# Sheet1.net
KiCad netlist of a schematic drawn in Altium Designer
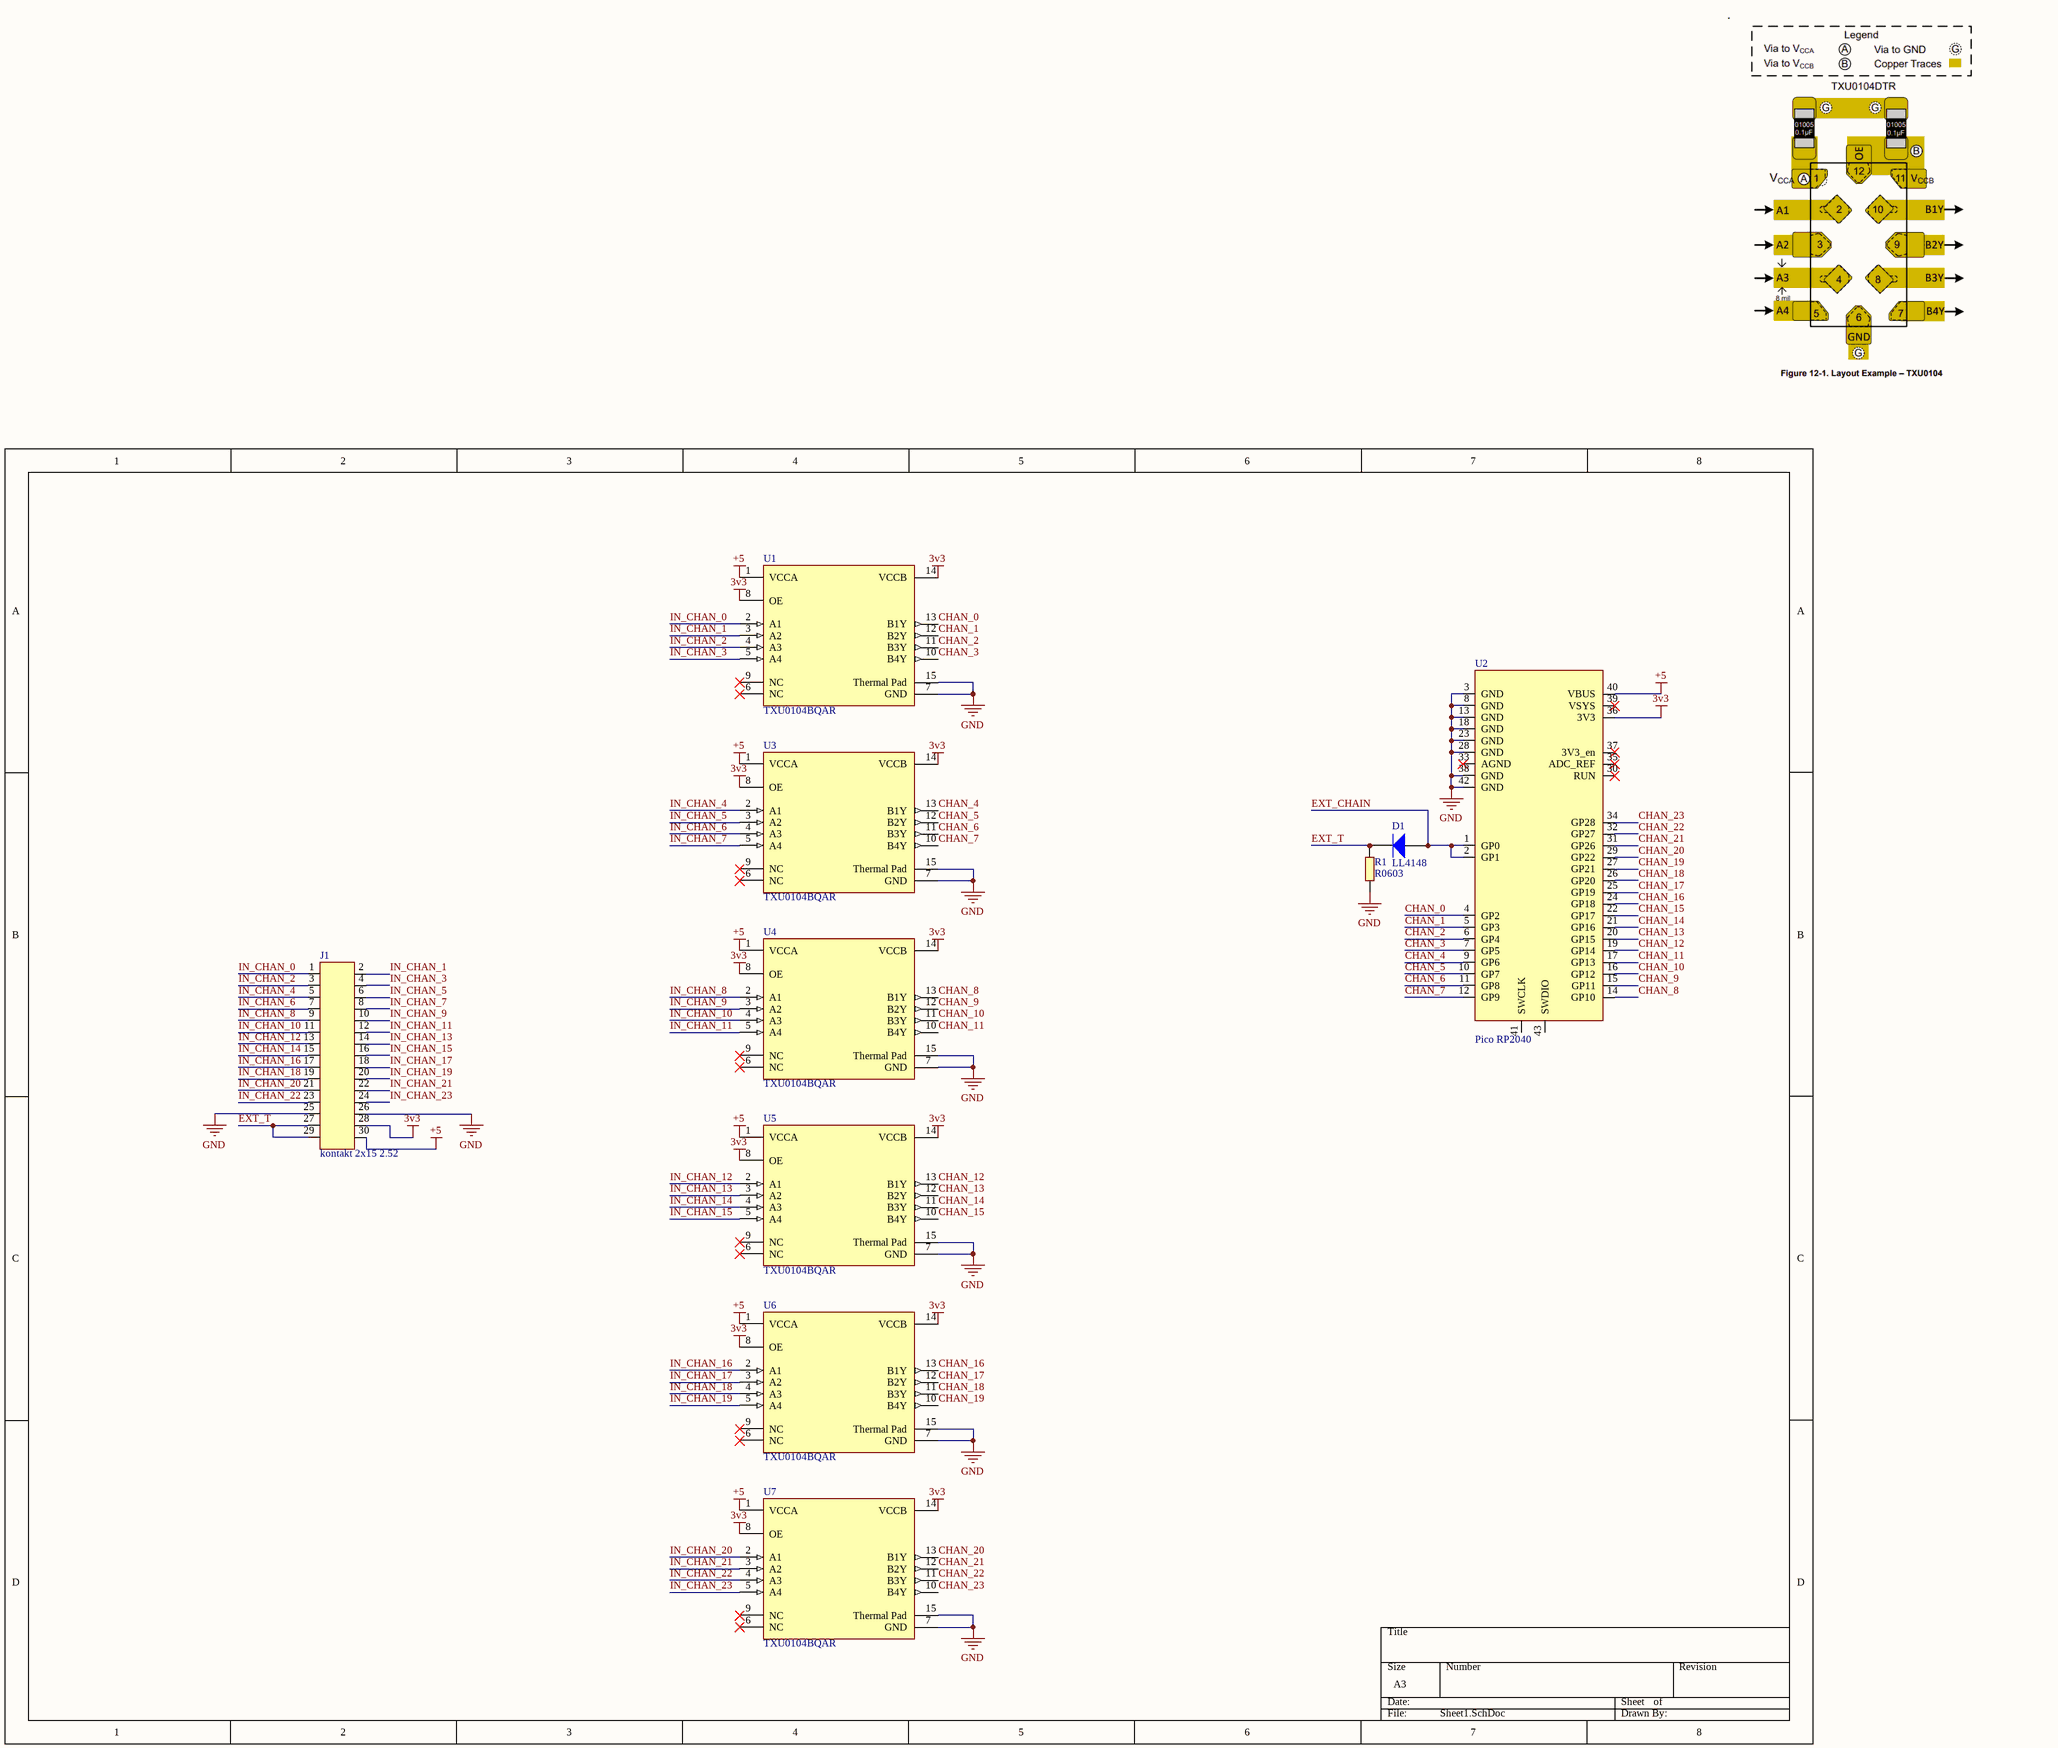
[diagram p0: Sheet1.SchDoc]

(export (version "E")
  (design (tool "Eeschema 10.0.6"))
  (components
    (comp (ref "D1")
      (value "LL4148")
      (footprint "FAIR-SOD80-2_V")
      (description "Small Signal Diode, 100 V, 0.2 A, -55 to 175 degC, 2-Pin SOD80, RoHS, Tape and Reel")
      (fields (field (name "MANUFACTURER") "Fairchild"))
      (libsource (lib "Altium Content Vault") (part "D-AK-2"))
    )
    (comp (ref "J1") (value "kontakt 2x15 2.52") (libsource (lib "Schlib1") (part "kontakt 2x15 2.52")))
    (comp (ref "R1") (value "R0603") (footprint "Res 0603") (libsource (lib "Schlib1") (part "R0603")))
    (comp (ref "U1")
      (value "TXU0104BQAR")
      (footprint "FP-BQA0014A-MFG")
      (description "FOUR CHANNEL UNIDIRECTIONAL LEVE")
      (libsource (lib "Altium Content Vault") (part "484c88173ff96930f3332f938e5da47"))
    )
    (comp (ref "U2")
      (value "Pico RP2040")
      (footprint "raspberry pico solder plate")
      (libsource (lib "Schlib1") (part "Pico RP2040"))
    )
    (comp (ref "U3")
      (value "TXU0104BQAR")
      (footprint "FP-BQA0014A-MFG")
      (description "FOUR CHANNEL UNIDIRECTIONAL LEVE")
      (libsource (lib "Altium Content Vault") (part "484c88173ff96930f3332f938e5da47"))
    )
    (comp (ref "U4")
      (value "TXU0104BQAR")
      (footprint "FP-BQA0014A-MFG")
      (description "FOUR CHANNEL UNIDIRECTIONAL LEVE")
      (libsource (lib "Altium Content Vault") (part "484c88173ff96930f3332f938e5da47"))
    )
    (comp (ref "U5")
      (value "TXU0104BQAR")
      (footprint "FP-BQA0014A-MFG")
      (description "FOUR CHANNEL UNIDIRECTIONAL LEVE")
      (libsource (lib "Altium Content Vault") (part "484c88173ff96930f3332f938e5da47"))
    )
    (comp (ref "U6")
      (value "TXU0104BQAR")
      (footprint "FP-BQA0014A-MFG")
      (description "FOUR CHANNEL UNIDIRECTIONAL LEVE")
      (libsource (lib "Altium Content Vault") (part "484c88173ff96930f3332f938e5da47"))
    )
    (comp (ref "U7")
      (value "TXU0104BQAR")
      (footprint "FP-BQA0014A-MFG")
      (description "FOUR CHANNEL UNIDIRECTIONAL LEVE")
      (libsource (lib "Altium Content Vault") (part "484c88173ff96930f3332f938e5da47"))
    )
  )
  (nets
    (net (code "1") (name "+5") (class "Default")
      (node (ref "J1") (pin "30") (pinfunction "30_30") (pintype "passive"))
      (node (ref "U1") (pin "1") (pinfunction "VCCA_1") (pintype "power_in"))
      (node (ref "U2") (pin "40") (pinfunction "VBUS_40") (pintype "passive"))
      (node (ref "U3") (pin "1") (pinfunction "VCCA_1") (pintype "power_in"))
      (node (ref "U4") (pin "1") (pinfunction "VCCA_1") (pintype "power_in"))
      (node (ref "U5") (pin "1") (pinfunction "VCCA_1") (pintype "power_in"))
      (node (ref "U6") (pin "1") (pinfunction "VCCA_1") (pintype "power_in"))
      (node (ref "U7") (pin "1") (pinfunction "VCCA_1") (pintype "power_in"))
    )
    (net (code "2") (name "/CHAN_0") (class "Default")
      (node (ref "U1") (pin "13") (pinfunction "B1Y_13") (pintype "output"))
      (node (ref "U2") (pin "4") (pinfunction "GP2_4") (pintype "passive"))
    )
    (net (code "3") (name "/CHAN_1") (class "Default")
      (node (ref "U1") (pin "12") (pinfunction "B2Y_12") (pintype "output"))
      (node (ref "U2") (pin "5") (pinfunction "GP3_5") (pintype "passive"))
    )
    (net (code "4") (name "/CHAN_2") (class "Default")
      (node (ref "U1") (pin "11") (pinfunction "B3Y_11") (pintype "output"))
      (node (ref "U2") (pin "6") (pinfunction "GP4_6") (pintype "passive"))
    )
    (net (code "5") (name "/CHAN_3") (class "Default")
      (node (ref "U1") (pin "10") (pinfunction "B4Y_10") (pintype "output"))
      (node (ref "U2") (pin "7") (pinfunction "GP5_7") (pintype "passive"))
    )
    (net (code "6") (name "/CHAN_4") (class "Default")
      (node (ref "U2") (pin "9") (pinfunction "GP6_9") (pintype "passive"))
      (node (ref "U3") (pin "13") (pinfunction "B1Y_13") (pintype "output"))
    )
    (net (code "7") (name "/CHAN_5") (class "Default")
      (node (ref "U2") (pin "10") (pinfunction "GP7_10") (pintype "passive"))
      (node (ref "U3") (pin "12") (pinfunction "B2Y_12") (pintype "output"))
    )
    (net (code "8") (name "/CHAN_6") (class "Default")
      (node (ref "U2") (pin "11") (pinfunction "GP8_11") (pintype "passive"))
      (node (ref "U3") (pin "11") (pinfunction "B3Y_11") (pintype "output"))
    )
    (net (code "9") (name "/CHAN_7") (class "Default")
      (node (ref "U2") (pin "12") (pinfunction "GP9_12") (pintype "passive"))
      (node (ref "U3") (pin "10") (pinfunction "B4Y_10") (pintype "output"))
    )
    (net (code "10") (name "/CHAN_8") (class "Default")
      (node (ref "U2") (pin "14") (pinfunction "GP10_14") (pintype "passive"))
      (node (ref "U4") (pin "13") (pinfunction "B1Y_13") (pintype "output"))
    )
    (net (code "11") (name "/CHAN_9") (class "Default")
      (node (ref "U2") (pin "15") (pinfunction "GP11_15") (pintype "passive"))
      (node (ref "U4") (pin "12") (pinfunction "B2Y_12") (pintype "output"))
    )
    (net (code "12") (name "/CHAN_10") (class "Default")
      (node (ref "U2") (pin "16") (pinfunction "GP12_16") (pintype "passive"))
      (node (ref "U4") (pin "11") (pinfunction "B3Y_11") (pintype "output"))
    )
    (net (code "13") (name "/CHAN_11") (class "Default")
      (node (ref "U2") (pin "17") (pinfunction "GP13_17") (pintype "passive"))
      (node (ref "U4") (pin "10") (pinfunction "B4Y_10") (pintype "output"))
    )
    (net (code "14") (name "/CHAN_12") (class "Default")
      (node (ref "U2") (pin "19") (pinfunction "GP14_19") (pintype "passive"))
      (node (ref "U5") (pin "13") (pinfunction "B1Y_13") (pintype "output"))
    )
    (net (code "15") (name "/CHAN_13") (class "Default")
      (node (ref "U2") (pin "20") (pinfunction "GP15_20") (pintype "passive"))
      (node (ref "U5") (pin "12") (pinfunction "B2Y_12") (pintype "output"))
    )
    (net (code "16") (name "/CHAN_14") (class "Default")
      (node (ref "U2") (pin "21") (pinfunction "GP16_21") (pintype "passive"))
      (node (ref "U5") (pin "11") (pinfunction "B3Y_11") (pintype "output"))
    )
    (net (code "17") (name "/CHAN_15") (class "Default")
      (node (ref "U2") (pin "22") (pinfunction "GP17_22") (pintype "passive"))
      (node (ref "U5") (pin "10") (pinfunction "B4Y_10") (pintype "output"))
    )
    (net (code "18") (name "/CHAN_16") (class "Default")
      (node (ref "U2") (pin "24") (pinfunction "GP18_24") (pintype "passive"))
      (node (ref "U6") (pin "13") (pinfunction "B1Y_13") (pintype "output"))
    )
    (net (code "19") (name "/CHAN_17") (class "Default")
      (node (ref "U2") (pin "25") (pinfunction "GP19_25") (pintype "passive"))
      (node (ref "U6") (pin "12") (pinfunction "B2Y_12") (pintype "output"))
    )
    (net (code "20") (name "/CHAN_18") (class "Default")
      (node (ref "U2") (pin "26") (pinfunction "GP20_26") (pintype "passive"))
      (node (ref "U6") (pin "11") (pinfunction "B3Y_11") (pintype "output"))
    )
    (net (code "21") (name "/CHAN_19") (class "Default")
      (node (ref "U2") (pin "27") (pinfunction "GP21_27") (pintype "passive"))
      (node (ref "U6") (pin "10") (pinfunction "B4Y_10") (pintype "output"))
    )
    (net (code "22") (name "/CHAN_20") (class "Default")
      (node (ref "U2") (pin "29") (pinfunction "GP22_29") (pintype "passive"))
      (node (ref "U7") (pin "13") (pinfunction "B1Y_13") (pintype "output"))
    )
    (net (code "23") (name "/CHAN_21") (class "Default")
      (node (ref "U2") (pin "31") (pinfunction "GP26_31") (pintype "passive"))
      (node (ref "U7") (pin "12") (pinfunction "B2Y_12") (pintype "output"))
    )
    (net (code "24") (name "/CHAN_22") (class "Default")
      (node (ref "U2") (pin "32") (pinfunction "GP27_32") (pintype "passive"))
      (node (ref "U7") (pin "11") (pinfunction "B3Y_11") (pintype "output"))
    )
    (net (code "25") (name "/CHAN_23") (class "Default")
      (node (ref "U2") (pin "34") (pinfunction "GP28_34") (pintype "passive"))
      (node (ref "U7") (pin "10") (pinfunction "B4Y_10") (pintype "output"))
    )
    (net (code "26") (name "/EXT_CHAIN") (class "Default")
      (node (ref "D1") (pin "1") (pinfunction "A_1") (pintype "passive"))
      (node (ref "U2") (pin "1") (pinfunction "GP0_1") (pintype "passive"))
      (node (ref "U2") (pin "2") (pinfunction "GP1_2") (pintype "passive"))
    )
    (net (code "27") (name "/EXT_T") (class "Default")
      (node (ref "D1") (pin "2") (pinfunction "K_2") (pintype "passive"))
      (node (ref "J1") (pin "27") (pinfunction "27_27") (pintype "passive"))
      (node (ref "J1") (pin "29") (pinfunction "29_29") (pintype "passive"))
      (node (ref "R1") (pin "2") (pinfunction "2_2") (pintype "passive"))
    )
    (net (code "28") (name "/IN_CHAN_0") (class "Default")
      (node (ref "J1") (pin "1") (pinfunction "1_1") (pintype "passive"))
      (node (ref "U1") (pin "2") (pinfunction "A1_2") (pintype "input"))
    )
    (net (code "29") (name "/IN_CHAN_1") (class "Default")
      (node (ref "J1") (pin "2") (pinfunction "2_2") (pintype "passive"))
      (node (ref "U1") (pin "3") (pinfunction "A2_3") (pintype "input"))
    )
    (net (code "30") (name "/IN_CHAN_2") (class "Default")
      (node (ref "J1") (pin "3") (pinfunction "3_3") (pintype "passive"))
      (node (ref "U1") (pin "4") (pinfunction "A3_4") (pintype "input"))
    )
    (net (code "31") (name "/IN_CHAN_3") (class "Default")
      (node (ref "J1") (pin "4") (pinfunction "4_4") (pintype "passive"))
      (node (ref "U1") (pin "5") (pinfunction "A4_5") (pintype "input"))
    )
    (net (code "32") (name "/IN_CHAN_4") (class "Default")
      (node (ref "J1") (pin "5") (pinfunction "5_5") (pintype "passive"))
      (node (ref "U3") (pin "2") (pinfunction "A1_2") (pintype "input"))
    )
    (net (code "33") (name "/IN_CHAN_5") (class "Default")
      (node (ref "J1") (pin "6") (pinfunction "6_6") (pintype "passive"))
      (node (ref "U3") (pin "3") (pinfunction "A2_3") (pintype "input"))
    )
    (net (code "34") (name "/IN_CHAN_6") (class "Default")
      (node (ref "J1") (pin "7") (pinfunction "7_7") (pintype "passive"))
      (node (ref "U3") (pin "4") (pinfunction "A3_4") (pintype "input"))
    )
    (net (code "35") (name "/IN_CHAN_7") (class "Default")
      (node (ref "J1") (pin "8") (pinfunction "8_8") (pintype "passive"))
      (node (ref "U3") (pin "5") (pinfunction "A4_5") (pintype "input"))
    )
    (net (code "36") (name "/IN_CHAN_8") (class "Default")
      (node (ref "J1") (pin "9") (pinfunction "9_9") (pintype "passive"))
      (node (ref "U4") (pin "2") (pinfunction "A1_2") (pintype "input"))
    )
    (net (code "37") (name "/IN_CHAN_9") (class "Default")
      (node (ref "J1") (pin "10") (pinfunction "10_10") (pintype "passive"))
      (node (ref "U4") (pin "3") (pinfunction "A2_3") (pintype "input"))
    )
    (net (code "38") (name "/IN_CHAN_10") (class "Default")
      (node (ref "J1") (pin "11") (pinfunction "11_11") (pintype "passive"))
      (node (ref "U4") (pin "4") (pinfunction "A3_4") (pintype "input"))
    )
    (net (code "39") (name "/IN_CHAN_11") (class "Default")
      (node (ref "J1") (pin "12") (pinfunction "12_12") (pintype "passive"))
      (node (ref "U4") (pin "5") (pinfunction "A4_5") (pintype "input"))
    )
    (net (code "40") (name "/IN_CHAN_12") (class "Default")
      (node (ref "J1") (pin "13") (pinfunction "13_13") (pintype "passive"))
      (node (ref "U5") (pin "2") (pinfunction "A1_2") (pintype "input"))
    )
    (net (code "41") (name "/IN_CHAN_13") (class "Default")
      (node (ref "J1") (pin "14") (pinfunction "14_14") (pintype "passive"))
      (node (ref "U5") (pin "3") (pinfunction "A2_3") (pintype "input"))
    )
    (net (code "42") (name "/IN_CHAN_14") (class "Default")
      (node (ref "J1") (pin "15") (pinfunction "15_15") (pintype "passive"))
      (node (ref "U5") (pin "4") (pinfunction "A3_4") (pintype "input"))
    )
    (net (code "43") (name "/IN_CHAN_15") (class "Default")
      (node (ref "J1") (pin "16") (pinfunction "16_16") (pintype "passive"))
      (node (ref "U5") (pin "5") (pinfunction "A4_5") (pintype "input"))
    )
    (net (code "44") (name "/IN_CHAN_16") (class "Default")
      (node (ref "J1") (pin "17") (pinfunction "17_17") (pintype "passive"))
      (node (ref "U6") (pin "2") (pinfunction "A1_2") (pintype "input"))
    )
    (net (code "45") (name "/IN_CHAN_17") (class "Default")
      (node (ref "J1") (pin "18") (pinfunction "18_18") (pintype "passive"))
      (node (ref "U6") (pin "3") (pinfunction "A2_3") (pintype "input"))
    )
    (net (code "46") (name "/IN_CHAN_18") (class "Default")
      (node (ref "J1") (pin "19") (pinfunction "19_19") (pintype "passive"))
      (node (ref "U6") (pin "4") (pinfunction "A3_4") (pintype "input"))
    )
    (net (code "47") (name "/IN_CHAN_19") (class "Default")
      (node (ref "J1") (pin "20") (pinfunction "20_20") (pintype "passive"))
      (node (ref "U6") (pin "5") (pinfunction "A4_5") (pintype "input"))
    )
    (net (code "48") (name "/IN_CHAN_20") (class "Default")
      (node (ref "J1") (pin "21") (pinfunction "21_21") (pintype "passive"))
      (node (ref "U7") (pin "2") (pinfunction "A1_2") (pintype "input"))
    )
    (net (code "49") (name "/IN_CHAN_21") (class "Default")
      (node (ref "J1") (pin "22") (pinfunction "22_22") (pintype "passive"))
      (node (ref "U7") (pin "3") (pinfunction "A2_3") (pintype "input"))
    )
    (net (code "50") (name "/IN_CHAN_22") (class "Default")
      (node (ref "J1") (pin "23") (pinfunction "23_23") (pintype "passive"))
      (node (ref "U7") (pin "4") (pinfunction "A3_4") (pintype "input"))
    )
    (net (code "51") (name "/IN_CHAN_23") (class "Default")
      (node (ref "J1") (pin "24") (pinfunction "24_24") (pintype "passive"))
      (node (ref "U7") (pin "5") (pinfunction "A4_5") (pintype "input"))
    )
    (net (code "52") (name "3v3") (class "Default")
      (node (ref "J1") (pin "28") (pinfunction "28_28") (pintype "passive"))
      (node (ref "U1") (pin "14") (pinfunction "VCCB_14") (pintype "power_in"))
      (node (ref "U1") (pin "8") (pinfunction "OE_8") (pintype "passive"))
      (node (ref "U2") (pin "36") (pinfunction "3V3_36") (pintype "passive"))
      (node (ref "U3") (pin "14") (pinfunction "VCCB_14") (pintype "power_in"))
      (node (ref "U3") (pin "8") (pinfunction "OE_8") (pintype "passive"))
      (node (ref "U4") (pin "14") (pinfunction "VCCB_14") (pintype "power_in"))
      (node (ref "U4") (pin "8") (pinfunction "OE_8") (pintype "passive"))
      (node (ref "U5") (pin "14") (pinfunction "VCCB_14") (pintype "power_in"))
      (node (ref "U5") (pin "8") (pinfunction "OE_8") (pintype "passive"))
      (node (ref "U6") (pin "14") (pinfunction "VCCB_14") (pintype "power_in"))
      (node (ref "U6") (pin "8") (pinfunction "OE_8") (pintype "passive"))
      (node (ref "U7") (pin "14") (pinfunction "VCCB_14") (pintype "power_in"))
      (node (ref "U7") (pin "8") (pinfunction "OE_8") (pintype "passive"))
    )
    (net (code "53") (name "GND") (class "Default")
      (node (ref "J1") (pin "25") (pinfunction "25_25") (pintype "passive"))
      (node (ref "J1") (pin "26") (pinfunction "26_26") (pintype "passive"))
      (node (ref "R1") (pin "1") (pinfunction "1_1") (pintype "passive"))
      (node (ref "U1") (pin "15") (pinfunction "Thermal_Pad_15") (pintype "power_in"))
      (node (ref "U1") (pin "7") (pinfunction "GND_7") (pintype "power_in"))
      (node (ref "U2") (pin "13") (pinfunction "GND_13") (pintype "passive"))
      (node (ref "U2") (pin "18") (pinfunction "GND_18") (pintype "passive"))
      (node (ref "U2") (pin "23") (pinfunction "GND_23") (pintype "passive"))
      (node (ref "U2") (pin "28") (pinfunction "GND_28") (pintype "passive"))
      (node (ref "U2") (pin "3") (pinfunction "GND_3") (pintype "passive"))
      (node (ref "U2") (pin "38") (pinfunction "GND_38") (pintype "passive"))
      (node (ref "U2") (pin "42") (pinfunction "GND_42") (pintype "passive"))
      (node (ref "U2") (pin "8") (pinfunction "GND_8") (pintype "passive"))
      (node (ref "U3") (pin "15") (pinfunction "Thermal_Pad_15") (pintype "power_in"))
      (node (ref "U3") (pin "7") (pinfunction "GND_7") (pintype "power_in"))
      (node (ref "U4") (pin "15") (pinfunction "Thermal_Pad_15") (pintype "power_in"))
      (node (ref "U4") (pin "7") (pinfunction "GND_7") (pintype "power_in"))
      (node (ref "U5") (pin "15") (pinfunction "Thermal_Pad_15") (pintype "power_in"))
      (node (ref "U5") (pin "7") (pinfunction "GND_7") (pintype "power_in"))
      (node (ref "U6") (pin "15") (pinfunction "Thermal_Pad_15") (pintype "power_in"))
      (node (ref "U6") (pin "7") (pinfunction "GND_7") (pintype "power_in"))
      (node (ref "U7") (pin "15") (pinfunction "Thermal_Pad_15") (pintype "power_in"))
      (node (ref "U7") (pin "7") (pinfunction "GND_7") (pintype "power_in"))
    )
    (net (code "54") (name "unconnected-(U1-NC-Pad6)") (class "Default")
      (node (ref "U1") (pin "6") (pinfunction "NC_6") (pintype "passive+no_connect"))
    )
    (net (code "55") (name "unconnected-(U1-NC-Pad9)") (class "Default")
      (node (ref "U1") (pin "9") (pinfunction "NC_9") (pintype "passive+no_connect"))
    )
    (net (code "56") (name "unconnected-(U2-3V3_en-Pad37)") (class "Default")
      (node (ref "U2") (pin "37") (pinfunction "3V3_en_37") (pintype "passive+no_connect"))
    )
    (net (code "57") (name "unconnected-(U2-ADC_REF-Pad35)") (class "Default")
      (node (ref "U2") (pin "35") (pinfunction "ADC_REF_35") (pintype "passive+no_connect"))
    )
    (net (code "58") (name "unconnected-(U2-AGND-Pad33)") (class "Default")
      (node (ref "U2") (pin "33") (pinfunction "AGND_33") (pintype "passive+no_connect"))
    )
    (net (code "59") (name "unconnected-(U2-RUN-Pad30)") (class "Default")
      (node (ref "U2") (pin "30") (pinfunction "RUN_30") (pintype "passive+no_connect"))
    )
    (net (code "60") (name "unconnected-(U2-SWCLK-Pad41)") (class "Default")
      (node (ref "U2") (pin "41") (pinfunction "SWCLK_41") (pintype "passive"))
    )
    (net (code "61") (name "unconnected-(U2-SWDIO-Pad43)") (class "Default")
      (node (ref "U2") (pin "43") (pinfunction "SWDIO_43") (pintype "passive"))
    )
    (net (code "62") (name "unconnected-(U2-VSYS-Pad39)") (class "Default")
      (node (ref "U2") (pin "39") (pinfunction "VSYS_39") (pintype "passive+no_connect"))
    )
    (net (code "63") (name "unconnected-(U3-NC-Pad6)") (class "Default")
      (node (ref "U3") (pin "6") (pinfunction "NC_6") (pintype "passive+no_connect"))
    )
    (net (code "64") (name "unconnected-(U3-NC-Pad9)") (class "Default")
      (node (ref "U3") (pin "9") (pinfunction "NC_9") (pintype "passive+no_connect"))
    )
    (net (code "65") (name "unconnected-(U4-NC-Pad6)") (class "Default")
      (node (ref "U4") (pin "6") (pinfunction "NC_6") (pintype "passive+no_connect"))
    )
    (net (code "66") (name "unconnected-(U4-NC-Pad9)") (class "Default")
      (node (ref "U4") (pin "9") (pinfunction "NC_9") (pintype "passive+no_connect"))
    )
    (net (code "67") (name "unconnected-(U5-NC-Pad6)") (class "Default")
      (node (ref "U5") (pin "6") (pinfunction "NC_6") (pintype "passive+no_connect"))
    )
    (net (code "68") (name "unconnected-(U5-NC-Pad9)") (class "Default")
      (node (ref "U5") (pin "9") (pinfunction "NC_9") (pintype "passive+no_connect"))
    )
    (net (code "69") (name "unconnected-(U6-NC-Pad6)") (class "Default")
      (node (ref "U6") (pin "6") (pinfunction "NC_6") (pintype "passive+no_connect"))
    )
    (net (code "70") (name "unconnected-(U6-NC-Pad9)") (class "Default")
      (node (ref "U6") (pin "9") (pinfunction "NC_9") (pintype "passive+no_connect"))
    )
    (net (code "71") (name "unconnected-(U7-NC-Pad6)") (class "Default")
      (node (ref "U7") (pin "6") (pinfunction "NC_6") (pintype "passive+no_connect"))
    )
    (net (code "72") (name "unconnected-(U7-NC-Pad9)") (class "Default")
      (node (ref "U7") (pin "9") (pinfunction "NC_9") (pintype "passive+no_connect"))
    )
  )
)
